# p06_sound.net
KiCad netlist of a schematic drawn in Altium Designer
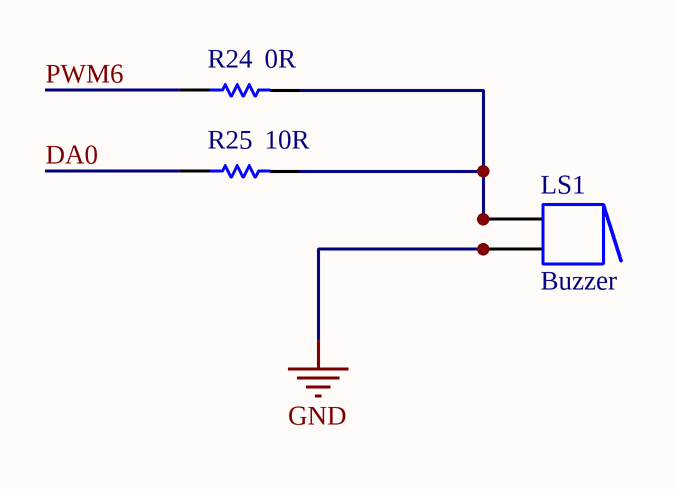
[diagram p0: p06_sound.SchDoc]

(export (version "E")
  (design (tool "Eeschema 10.0.6"))
  (components
    (comp (ref "LS1")
      (value "Buzzer")
      (footprint "HDR1X2")
      (description "Magnetic Transducer Buzzer")
      (fields (field (name "PUBLISHER") "Altium Limited"))
      (libsource (lib "Miscellaneous Devices") (part "Buzzer"))
    )
    (comp (ref "R24")
      (value "0R")
      (footprint "6-0805_M")
      (description "Resistor")
      (fields (field (name "Comment") "Res1") (field (name "PUBLISHER") "Altium Limited"))
      (libsource (lib "Miscellaneous Devices") (part "Res1"))
    )
    (comp (ref "R25")
      (value "10R")
      (footprint "6-0805_M")
      (description "Resistor")
      (fields (field (name "Comment") "Res1") (field (name "PUBLISHER") "Altium Limited"))
      (libsource (lib "Miscellaneous Devices") (part "Res1"))
    )
  )
  (nets
    (net (code "1") (name "/DA0") (class "Default")
      (node (ref "R25") (pin "1") (pinfunction "1_1") (pintype "passive"))
    )
    (net (code "2") (name "/PWM6") (class "Default")
      (node (ref "R24") (pin "1") (pinfunction "1_1") (pintype "passive"))
    )
    (net (code "3") (name "GND") (class "Default")
      (node (ref "LS1") (pin "2") (pinfunction "2_2") (pintype "passive"))
      (node (ref "LS1") (pin "2A") (pinfunction "2A_2A") (pintype "passive"))
    )
    (net (code "4") (name "Net-(LS1-Pad1)") (class "Default")
      (node (ref "LS1") (pin "1") (pinfunction "1_1") (pintype "passive"))
      (node (ref "LS1") (pin "1A") (pinfunction "1A_1A") (pintype "passive"))
      (node (ref "R24") (pin "2") (pinfunction "2_2") (pintype "passive"))
      (node (ref "R25") (pin "2") (pinfunction "2_2") (pintype "passive"))
    )
  )
)
